# CO2_Sensor_V1_0.net
KiCad netlist of a schematic drawn in EAGLE
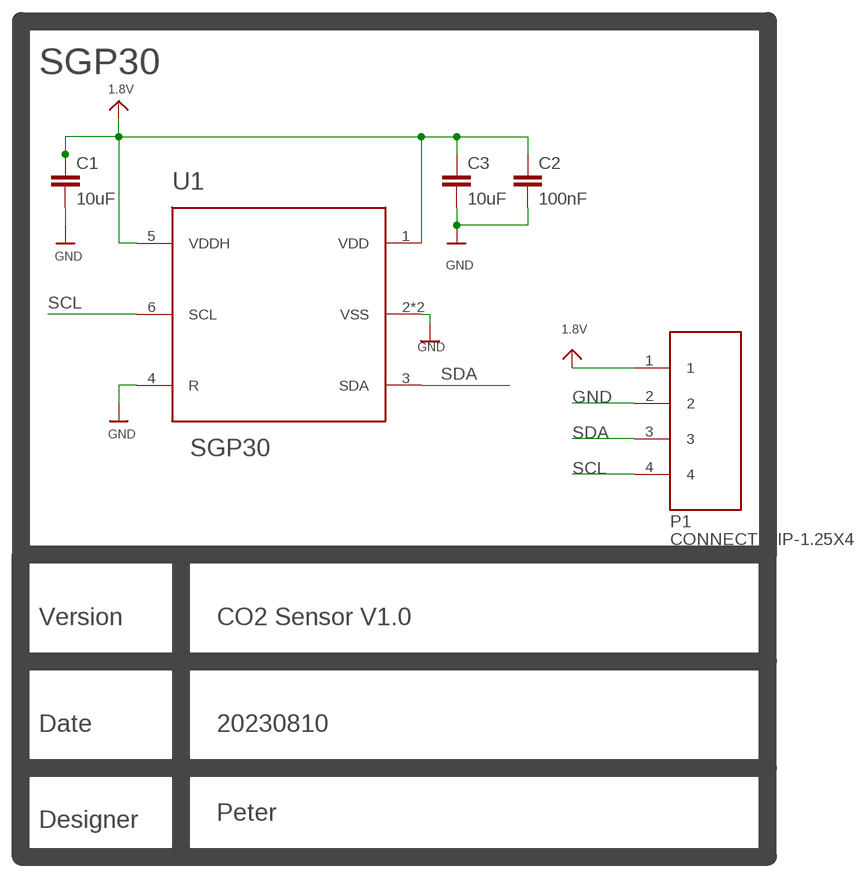
[diagram p0: schematic, sheet 1]

(export (version "E")
  (design (tool "Eeschema 10.0.6"))
  (components
    (comp (ref "C1")
      (value "10uF")
      (footprint "eagle-import:C0603")
      (libsource (lib "eagle-import") (part "C0603"))
    )
    (comp (ref "C2")
      (value "100nF")
      (footprint "eagle-import:C0603")
      (libsource (lib "eagle-import") (part "C0603"))
    )
    (comp (ref "C3")
      (value "10uF")
      (footprint "eagle-import:C0603")
      (libsource (lib "eagle-import") (part "C0603"))
    )
    (comp (ref "P1")
      (value "CONNECT-DIP-1.25X4")
      (footprint "eagle-import:CONNECT-DIP-1.25X4")
      (libsource (lib "eagle-import") (part "CONNECT-DIP-1.25X4"))
    )
    (comp (ref "U1")
      (value "SGP30")
      (footprint "eagle-import:SGP30")
      (libsource (lib "eagle-import") (part "SGP30"))
    )
  )
  (nets
    (net (code "1") (name "/SCL") (class "Default")
      (node (ref "P1") (pin "4") (pinfunction "4_4") (pintype "bidirectional"))
      (node (ref "U1") (pin "6") (pinfunction "SCL_6") (pintype "bidirectional"))
    )
    (net (code "2") (name "/SDA") (class "Default")
      (node (ref "P1") (pin "3") (pinfunction "3_3") (pintype "bidirectional"))
      (node (ref "U1") (pin "3") (pinfunction "SDA_3") (pintype "bidirectional"))
    )
    (net (code "3") (name "1.8V") (class "Default")
      (node (ref "C1") (pin "1") (pinfunction "1_1") (pintype "passive"))
      (node (ref "C2") (pin "1") (pinfunction "1_1") (pintype "passive"))
      (node (ref "C3") (pin "1") (pinfunction "1_1") (pintype "passive"))
      (node (ref "P1") (pin "1") (pinfunction "1_1") (pintype "bidirectional"))
      (node (ref "U1") (pin "1") (pinfunction "VDD_1") (pintype "bidirectional"))
      (node (ref "U1") (pin "5") (pinfunction "VDDH_5") (pintype "bidirectional"))
    )
    (net (code "4") (name "GND") (class "Default")
      (node (ref "C1") (pin "2") (pinfunction "2_2") (pintype "passive"))
      (node (ref "C2") (pin "2") (pinfunction "2_2") (pintype "passive"))
      (node (ref "C3") (pin "2") (pinfunction "2_2") (pintype "passive"))
      (node (ref "P1") (pin "2") (pinfunction "2_2") (pintype "bidirectional"))
      (node (ref "U1") (pin "2") (pinfunction "VSS_2") (pintype "bidirectional"))
      (node (ref "U1") (pin "4") (pinfunction "R_4") (pintype "bidirectional"))
      (node (ref "U1") (pin "P$7") (pinfunction "VSS_P$7") (pintype "bidirectional"))
    )
  )
)
